# powermodule.net
KiCad netlist of a schematic drawn in EAGLE
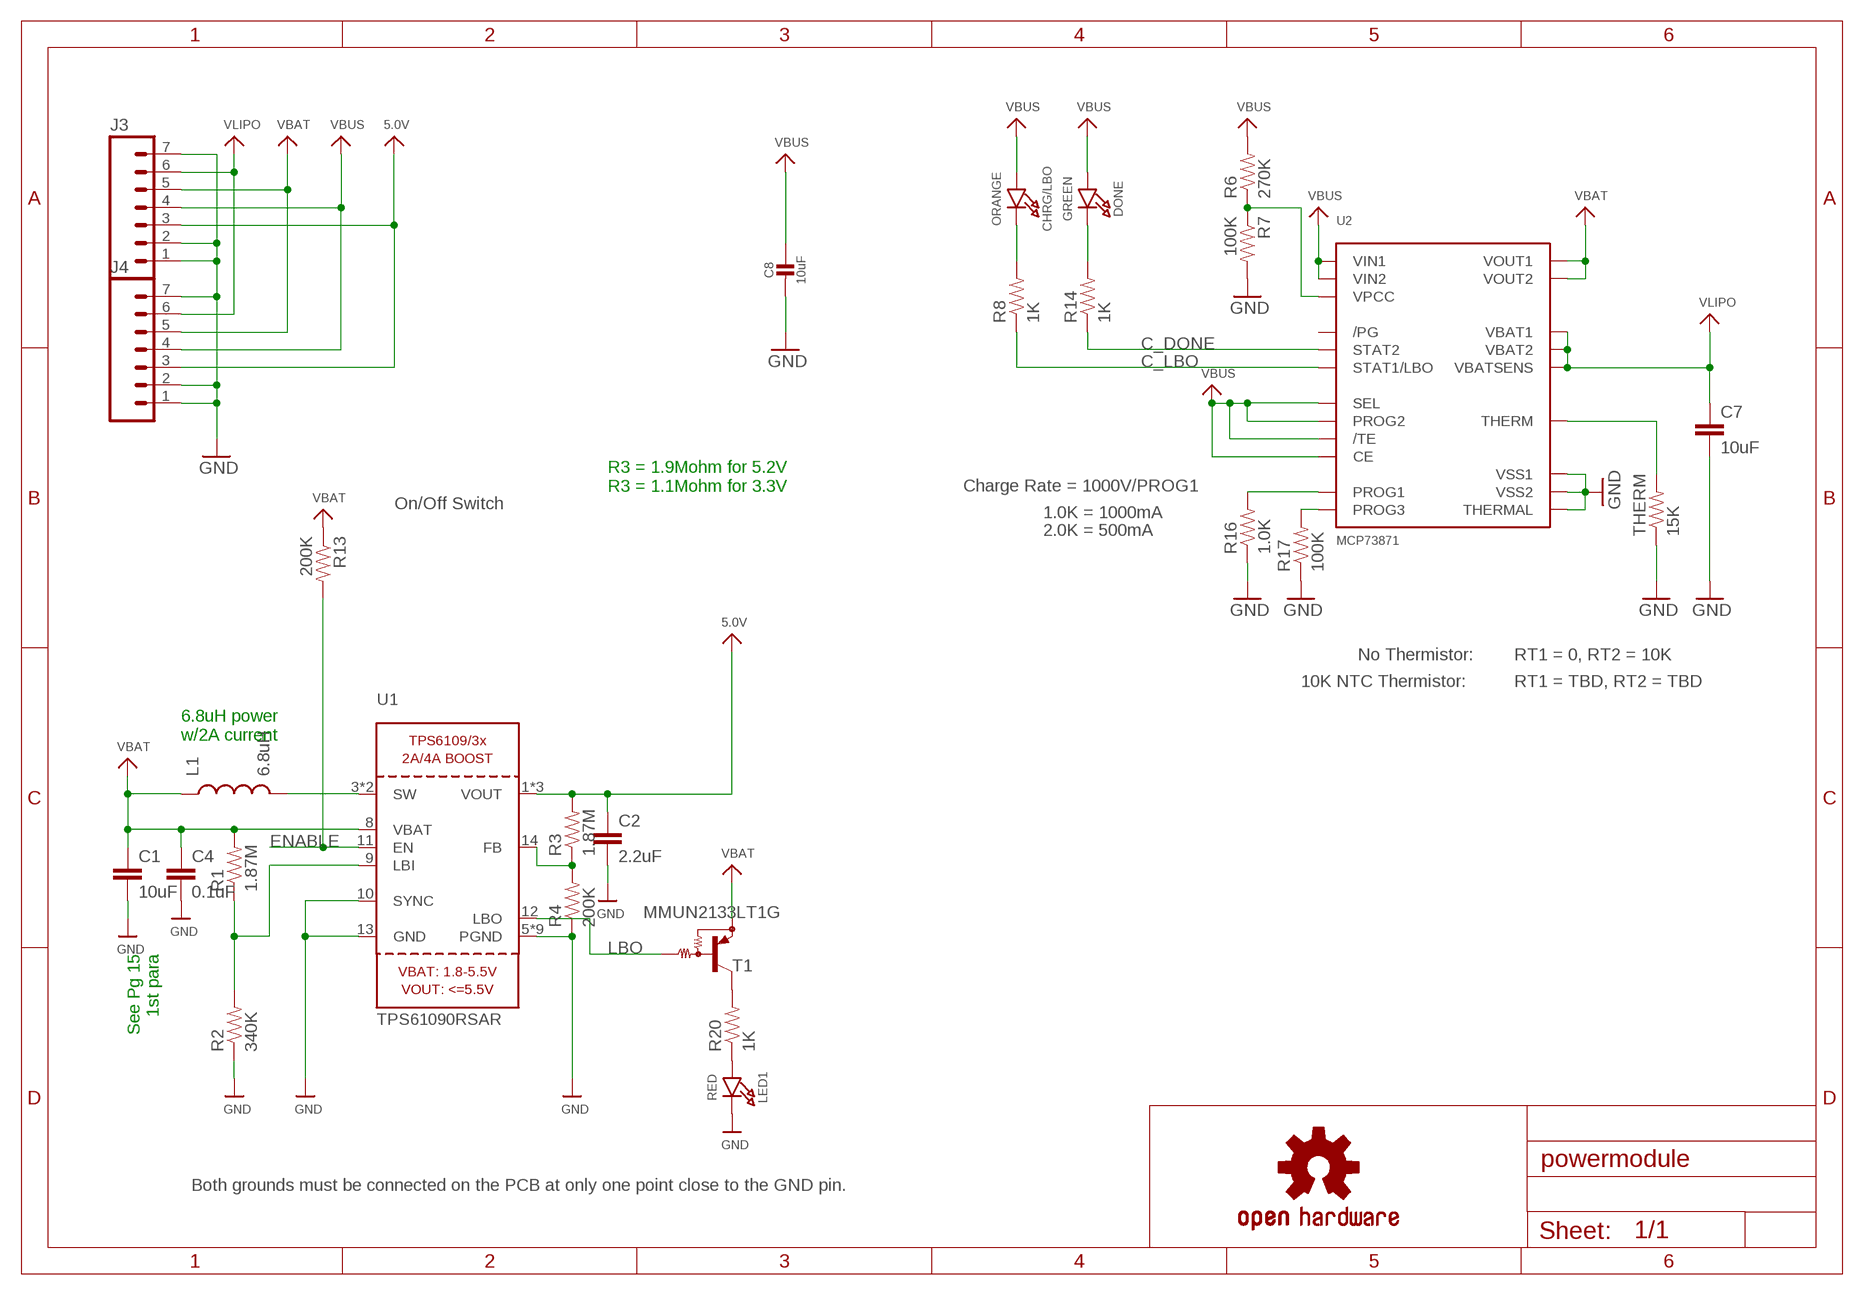
[diagram p0: schematic, sheet 1]

(export (version "E")
  (design (tool "Eeschema 10.0.6"))
  (components
    (comp (ref "C1")
      (value "10uF")
      (footprint "eagle-import:0603-CAP")
      (libsource (lib "eagle-import") (part "CAP0603-CAP"))
    )
    (comp (ref "C2")
      (value "2.2uF")
      (footprint "eagle-import:0603-CAP")
      (libsource (lib "eagle-import") (part "CAP0603-CAP"))
    )
    (comp (ref "C4")
      (value "0.1uF")
      (footprint "eagle-import:0603-CAP")
      (libsource (lib "eagle-import") (part "CAP0603-CAP"))
    )
    (comp (ref "C7")
      (value "10uF")
      (footprint "eagle-import:0603-CAP")
      (libsource (lib "eagle-import") (part "CAP0603-CAP"))
    )
    (comp (ref "C8")
      (value "10uF")
      (footprint "eagle-import:0805-NO")
      (libsource (lib "eagle-import") (part "CAP_CERAMIC0805-NOOUTLINE"))
    )
    (comp (ref "CHRG/LBO")
      (value "ORANGE")
      (footprint "eagle-import:CHIPLED_0805_NOOUTLINE")
      (libsource (lib "eagle-import") (part "LED0805_NOOUTLINE"))
    )
    (comp (ref "DONE")
      (value "GREEN")
      (footprint "eagle-import:CHIPLED_0805_NOOUTLINE")
      (libsource (lib "eagle-import") (part "LED0805_NOOUTLINE"))
    )
    (comp (ref "J3")
      (value "M07")
      (footprint "eagle-import:1X07")
      (libsource (lib "eagle-import") (part "M07"))
    )
    (comp (ref "J4")
      (value "M07")
      (footprint "eagle-import:1X07")
      (libsource (lib "eagle-import") (part "M07"))
    )
    (comp (ref "L1")
      (value "6.8uH")
      (footprint "eagle-import:SRU5028")
      (libsource (lib "eagle-import") (part "INDUCTORSRU5028"))
    )
    (comp (ref "LED1")
      (value "RED")
      (footprint "eagle-import:CHIPLED_0805_NOOUTLINE")
      (libsource (lib "eagle-import") (part "LED0805_NOOUTLINE"))
    )
    (comp (ref "LOGO1")
      (value "OSHW-LOGOS")
      (footprint "eagle-import:OSHW-LOGO-S")
      (libsource (lib "eagle-import") (part "OSHW-LOGOS"))
    )
    (comp (ref "R1")
      (value "1.87M")
      (footprint "eagle-import:0603-RES")
      (libsource (lib "eagle-import") (part "RESISTOR0603-RES"))
    )
    (comp (ref "R2")
      (value "340K")
      (footprint "eagle-import:0603-RES")
      (libsource (lib "eagle-import") (part "RESISTOR0603-RES"))
    )
    (comp (ref "R3")
      (value "1.87M")
      (footprint "eagle-import:0603-RES")
      (libsource (lib "eagle-import") (part "RESISTOR0603-RES"))
    )
    (comp (ref "R4")
      (value "200K")
      (footprint "eagle-import:0603-RES")
      (libsource (lib "eagle-import") (part "RESISTOR0603-RES"))
    )
    (comp (ref "R6")
      (value "270K")
      (footprint "eagle-import:0603-RES")
      (libsource (lib "eagle-import") (part "RESISTOR0603-RES"))
    )
    (comp (ref "R7")
      (value "100K")
      (footprint "eagle-import:0603-RES")
      (libsource (lib "eagle-import") (part "RESISTOR0603-RES"))
    )
    (comp (ref "R8")
      (value "1K")
      (footprint "eagle-import:0603-RES")
      (libsource (lib "eagle-import") (part "RESISTOR0603-RES"))
    )
    (comp (ref "R13")
      (value "200K")
      (footprint "eagle-import:0603-RES")
      (libsource (lib "eagle-import") (part "RESISTOR0603-RES"))
    )
    (comp (ref "R14")
      (value "1K")
      (footprint "eagle-import:0603-RES")
      (libsource (lib "eagle-import") (part "RESISTOR0603-RES"))
    )
    (comp (ref "R16")
      (value "1.0K")
      (footprint "eagle-import:0603-RES")
      (libsource (lib "eagle-import") (part "RESISTOR0603-RES"))
    )
    (comp (ref "R17")
      (value "100K")
      (footprint "eagle-import:0603-RES")
      (libsource (lib "eagle-import") (part "RESISTOR0603-RES"))
    )
    (comp (ref "R20")
      (value "1K")
      (footprint "eagle-import:0603-RES")
      (libsource (lib "eagle-import") (part "RESISTOR0603-RES"))
    )
    (comp (ref "T1")
      (value "MMUN2133LT1G")
      (footprint "eagle-import:SC59-BEC")
      (libsource (lib "eagle-import") (part "-PNP_DRIVER-SC59-BECMUN2114T1"))
    )
    (comp (ref "THERM")
      (value "15K")
      (footprint "eagle-import:0603-RES")
      (libsource (lib "eagle-import") (part "RESISTOR0603-RES"))
    )
    (comp (ref "U1")
      (value "TPS61090RSAR")
      (footprint "eagle-import:PVQFN-16")
      (libsource (lib "eagle-import") (part "VREG_TPS6103X"))
    )
    (comp (ref "U2")
      (value "MCP73871")
      (footprint "eagle-import:QFN20_4MM")
      (libsource (lib "eagle-import") (part "MCP73871"))
    )
  )
  (nets
    (net (code "1") (name "/C_DONE") (class "Default")
      (node (ref "R14") (pin "1") (pinfunction "1_1") (pintype "passive"))
      (node (ref "U2") (pin "P$7") (pinfunction "STAT2_P$7") (pintype "bidirectional"))
    )
    (net (code "2") (name "/C_LBO") (class "Default")
      (node (ref "R8") (pin "1") (pinfunction "1_1") (pintype "passive"))
      (node (ref "U2") (pin "P$8") (pinfunction "STAT1/LBO_P$8") (pintype "bidirectional"))
    )
    (net (code "3") (name "/ENABLE") (class "Default")
      (node (ref "R13") (pin "2") (pinfunction "2_2") (pintype "passive"))
      (node (ref "U1") (pin "11") (pinfunction "EN_11") (pintype "input"))
    )
    (net (code "4") (name "/LBO") (class "Default")
      (node (ref "T1") (pin "B") (pinfunction "B_B") (pintype "passive"))
      (node (ref "U1") (pin "12") (pinfunction "LBO_12") (pintype "output"))
    )
    (net (code "5") (name "5.0V") (class "Default")
      (node (ref "C2") (pin "1") (pinfunction "1_1") (pintype "passive"))
      (node (ref "J3") (pin "3") (pinfunction "3_3") (pintype "passive"))
      (node (ref "J4") (pin "3") (pinfunction "3_3") (pintype "passive"))
      (node (ref "R3") (pin "2") (pinfunction "2_2") (pintype "passive"))
      (node (ref "U1") (pin "1") (pinfunction "VOUT_1") (pintype "power_in"))
      (node (ref "U1") (pin "15") (pinfunction "VOUT_15") (pintype "power_in"))
      (node (ref "U1") (pin "16") (pinfunction "VOUT_16") (pintype "power_in"))
    )
    (net (code "6") (name "GND") (class "Default")
      (node (ref "C1") (pin "2") (pinfunction "2_2") (pintype "passive"))
      (node (ref "C2") (pin "2") (pinfunction "2_2") (pintype "passive"))
      (node (ref "C4") (pin "2") (pinfunction "2_2") (pintype "passive"))
      (node (ref "C7") (pin "2") (pinfunction "2_2") (pintype "passive"))
      (node (ref "C8") (pin "2") (pinfunction "2_2") (pintype "passive"))
      (node (ref "J3") (pin "1") (pinfunction "1_1") (pintype "passive"))
      (node (ref "J3") (pin "2") (pinfunction "2_2") (pintype "passive"))
      (node (ref "J3") (pin "7") (pinfunction "7_7") (pintype "passive"))
      (node (ref "J4") (pin "1") (pinfunction "1_1") (pintype "passive"))
      (node (ref "J4") (pin "2") (pinfunction "2_2") (pintype "passive"))
      (node (ref "J4") (pin "7") (pinfunction "7_7") (pintype "passive"))
      (node (ref "LED1") (pin "C") (pinfunction "C_C") (pintype "passive"))
      (node (ref "R16") (pin "1") (pinfunction "1_1") (pintype "passive"))
      (node (ref "R17") (pin "1") (pinfunction "1_1") (pintype "passive"))
      (node (ref "R2") (pin "1") (pinfunction "1_1") (pintype "passive"))
      (node (ref "R4") (pin "1") (pinfunction "1_1") (pintype "passive"))
      (node (ref "R7") (pin "2") (pinfunction "2_2") (pintype "passive"))
      (node (ref "THERM") (pin "1") (pinfunction "1_1") (pintype "passive"))
      (node (ref "U1") (pin "10") (pinfunction "SYNC_10") (pintype "input"))
      (node (ref "U1") (pin "13") (pinfunction "GND_13") (pintype "power_in"))
      (node (ref "U1") (pin "5") (pinfunction "PGND_5") (pintype "power_in"))
      (node (ref "U1") (pin "6") (pinfunction "PGND_6") (pintype "power_in"))
      (node (ref "U1") (pin "7") (pinfunction "PGND_7") (pintype "power_in"))
      (node (ref "U1") (pin "P$18") (pinfunction "PGND_P$18") (pintype "power_in"))
      (node (ref "U1") (pin "P$19") (pinfunction "PGND_P$19") (pintype "power_in"))
      (node (ref "U1") (pin "P$20") (pinfunction "PGND_P$20") (pintype "power_in"))
      (node (ref "U1") (pin "P$21") (pinfunction "PGND_P$21") (pintype "power_in"))
      (node (ref "U1") (pin "P$22") (pinfunction "PGND_P$22") (pintype "power_in"))
      (node (ref "U1") (pin "THERMAL") (pinfunction "PGND_THERMAL") (pintype "power_in"))
      (node (ref "U2") (pin "P$10") (pinfunction "VSS1_P$10") (pintype "bidirectional"))
      (node (ref "U2") (pin "P$11") (pinfunction "VSS2_P$11") (pintype "bidirectional"))
      (node (ref "U2") (pin "P$21") (pinfunction "THERMAL_P$21") (pintype "bidirectional"))
    )
    (net (code "7") (name "Net-(CHRG/LBO-PadC)") (class "Default")
      (node (ref "CHRG/LBO") (pin "C") (pinfunction "C_C") (pintype "passive"))
      (node (ref "R8") (pin "2") (pinfunction "2_2") (pintype "passive"))
    )
    (net (code "8") (name "Net-(DONE-PadC)") (class "Default")
      (node (ref "DONE") (pin "C") (pinfunction "C_C") (pintype "passive"))
      (node (ref "R14") (pin "2") (pinfunction "2_2") (pintype "passive"))
    )
    (net (code "9") (name "Net-(L1-Pad2)") (class "Default")
      (node (ref "L1") (pin "2") (pinfunction "2_2") (pintype "passive"))
      (node (ref "U1") (pin "3") (pinfunction "SW_3") (pintype "input"))
      (node (ref "U1") (pin "4") (pinfunction "SW_4") (pintype "input"))
    )
    (net (code "10") (name "Net-(LED1-PadA)") (class "Default")
      (node (ref "LED1") (pin "A") (pinfunction "A_A") (pintype "passive"))
      (node (ref "R20") (pin "1") (pinfunction "1_1") (pintype "passive"))
    )
    (net (code "11") (name "Net-(R20-Pad2)") (class "Default")
      (node (ref "R20") (pin "2") (pinfunction "2_2") (pintype "passive"))
      (node (ref "T1") (pin "C") (pinfunction "C_C") (pintype "passive"))
    )
    (net (code "12") (name "Net-(U1-FB)") (class "Default")
      (node (ref "R3") (pin "1") (pinfunction "1_1") (pintype "passive"))
      (node (ref "R4") (pin "2") (pinfunction "2_2") (pintype "passive"))
      (node (ref "U1") (pin "14") (pinfunction "FB_14") (pintype "input"))
    )
    (net (code "13") (name "Net-(U1-LBI)") (class "Default")
      (node (ref "R1") (pin "1") (pinfunction "1_1") (pintype "passive"))
      (node (ref "R2") (pin "2") (pinfunction "2_2") (pintype "passive"))
      (node (ref "U1") (pin "9") (pinfunction "LBI_9") (pintype "input"))
    )
    (net (code "14") (name "Net-(U2-PROG1)") (class "Default")
      (node (ref "R16") (pin "2") (pinfunction "2_2") (pintype "passive"))
      (node (ref "U2") (pin "P$13") (pinfunction "PROG1_P$13") (pintype "bidirectional"))
    )
    (net (code "15") (name "Net-(U2-PROG3)") (class "Default")
      (node (ref "R17") (pin "2") (pinfunction "2_2") (pintype "passive"))
      (node (ref "U2") (pin "P$12") (pinfunction "PROG3_P$12") (pintype "bidirectional"))
    )
    (net (code "16") (name "Net-(U2-THERM)") (class "Default")
      (node (ref "THERM") (pin "2") (pinfunction "2_2") (pintype "passive"))
      (node (ref "U2") (pin "P$5") (pinfunction "THERM_P$5") (pintype "bidirectional"))
    )
    (net (code "17") (name "Net-(U2-VPCC)") (class "Default")
      (node (ref "R6") (pin "1") (pinfunction "1_1") (pintype "passive"))
      (node (ref "R7") (pin "1") (pinfunction "1_1") (pintype "passive"))
      (node (ref "U2") (pin "P$2") (pinfunction "VPCC_P$2") (pintype "bidirectional"))
    )
    (net (code "18") (name "VBAT") (class "Default")
      (node (ref "C1") (pin "1") (pinfunction "1_1") (pintype "passive"))
      (node (ref "C4") (pin "1") (pinfunction "1_1") (pintype "passive"))
      (node (ref "J3") (pin "5") (pinfunction "5_5") (pintype "passive"))
      (node (ref "J4") (pin "5") (pinfunction "5_5") (pintype "passive"))
      (node (ref "L1") (pin "1") (pinfunction "1_1") (pintype "passive"))
      (node (ref "R1") (pin "2") (pinfunction "2_2") (pintype "passive"))
      (node (ref "R13") (pin "1") (pinfunction "1_1") (pintype "passive"))
      (node (ref "T1") (pin "E") (pinfunction "E_E") (pintype "passive"))
      (node (ref "U1") (pin "8") (pinfunction "VBAT_8") (pintype "input"))
      (node (ref "U2") (pin "P$1") (pinfunction "VOUT1_P$1") (pintype "bidirectional"))
      (node (ref "U2") (pin "P$20") (pinfunction "VOUT2_P$20") (pintype "bidirectional"))
    )
    (net (code "19") (name "VBUS") (class "Default")
      (node (ref "C8") (pin "1") (pinfunction "1_1") (pintype "passive"))
      (node (ref "CHRG/LBO") (pin "A") (pinfunction "A_A") (pintype "passive"))
      (node (ref "DONE") (pin "A") (pinfunction "A_A") (pintype "passive"))
      (node (ref "J3") (pin "4") (pinfunction "4_4") (pintype "passive"))
      (node (ref "J4") (pin "4") (pinfunction "4_4") (pintype "passive"))
      (node (ref "R6") (pin "2") (pinfunction "2_2") (pintype "passive"))
      (node (ref "U2") (pin "P$17") (pinfunction "CE_P$17") (pintype "bidirectional"))
      (node (ref "U2") (pin "P$18") (pinfunction "VIN1_P$18") (pintype "bidirectional"))
      (node (ref "U2") (pin "P$19") (pinfunction "VIN2_P$19") (pintype "bidirectional"))
      (node (ref "U2") (pin "P$3") (pinfunction "SEL_P$3") (pintype "bidirectional"))
      (node (ref "U2") (pin "P$4") (pinfunction "PROG2_P$4") (pintype "bidirectional"))
      (node (ref "U2") (pin "P$9") (pinfunction "/TE_P$9") (pintype "bidirectional"))
    )
    (net (code "20") (name "VLIPO") (class "Default")
      (node (ref "C7") (pin "1") (pinfunction "1_1") (pintype "passive"))
      (node (ref "J3") (pin "6") (pinfunction "6_6") (pintype "passive"))
      (node (ref "J4") (pin "6") (pinfunction "6_6") (pintype "passive"))
      (node (ref "U2") (pin "P$14") (pinfunction "VBAT1_P$14") (pintype "bidirectional"))
      (node (ref "U2") (pin "P$15") (pinfunction "VBAT2_P$15") (pintype "bidirectional"))
      (node (ref "U2") (pin "P$16") (pinfunction "VBATSENS_P$16") (pintype "bidirectional"))
    )
    (net (code "21") (name "unconnected-(U2-{slash}PG-PadP$6)") (class "Default")
      (node (ref "U2") (pin "P$6") (pinfunction "/PG_P$6") (pintype "bidirectional"))
    )
  )
)
